# SCH_MODULO_LORA.net
KiCad netlist of a schematic drawn in Altium Designer
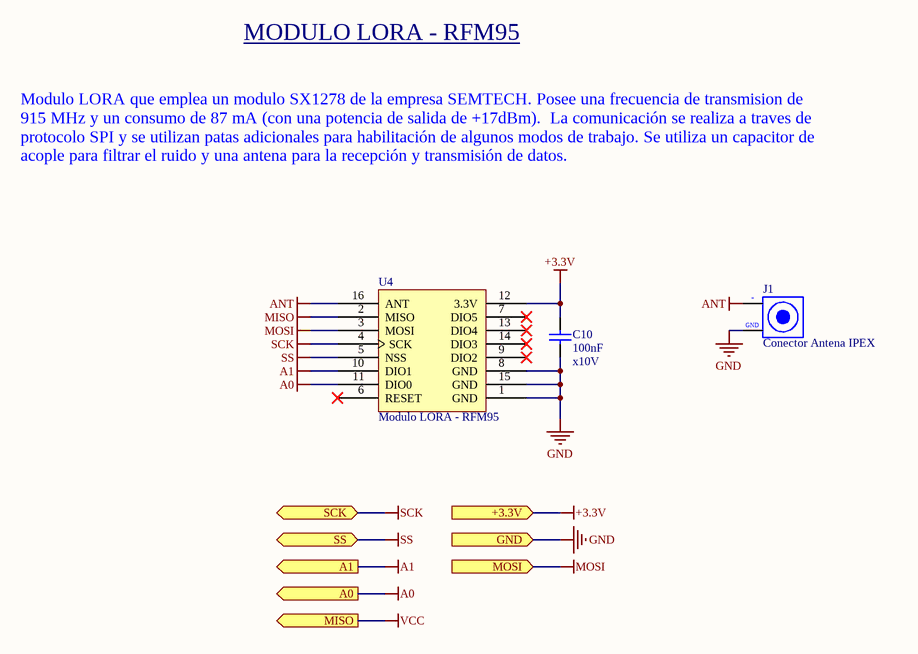
[diagram p0: SCH_MODULO_LORA.SchDoc]

(export (version "E")
  (design (tool "Eeschema 10.0.6"))
  (components
    (comp (ref "C10")
      (value "100nF")
      (footprint "RAD-0.3")
      (description "Capacitor")
      (fields
        (field (name "VOLTAGE") "x10V")
        (field (name "Comment") "Capacitor - Común")
        (field (name "PUBLISHER") "Altium Limited")
      )
      (libsource (lib "LIB_COLLAR") (part "Capacitor - Común"))
    )
    (comp (ref "J1")
      (value "Conector Antena IPEX")
      (description "IPEX MHF3")
      (libsource (lib "LIB_COLLAR") (part "Conector Antena IPEX"))
    )
    (comp (ref "U4")
      (value "Modulo LORA - RFM95")
      (description "RFM95-915-S2")
      (libsource (lib "LIB_COLLAR") (part "Modulo LORA - RFM95"))
    )
  )
  (nets
    (net (code "1") (name "+3.3V") (class "Default")
      (node (ref "C10") (pin "2") (pinfunction "2_2") (pintype "passive"))
      (node (ref "U4") (pin "12") (pinfunction "3.3V_12") (pintype "passive"))
    )
    (net (code "2") (name "A0") (class "Default")
      (node (ref "U4") (pin "11") (pinfunction "DIO0_11") (pintype "passive"))
    )
    (net (code "3") (name "A1") (class "Default")
      (node (ref "U4") (pin "10") (pinfunction "DIO1_10") (pintype "passive"))
    )
    (net (code "4") (name "ANT") (class "Default")
      (node (ref "J1") (pin "1") (pinfunction "ANT_1") (pintype "passive"))
      (node (ref "U4") (pin "16") (pinfunction "ANT_16") (pintype "passive"))
    )
    (net (code "5") (name "GND") (class "Default")
      (node (ref "C10") (pin "1") (pinfunction "1_1") (pintype "passive"))
      (node (ref "J1") (pin "2") (pinfunction "2_2") (pintype "passive"))
      (node (ref "U4") (pin "1") (pinfunction "GND_1") (pintype "passive"))
      (node (ref "U4") (pin "15") (pinfunction "GND_15") (pintype "passive"))
      (node (ref "U4") (pin "8") (pinfunction "GND_8") (pintype "passive"))
    )
    (net (code "6") (name "MISO") (class "Default")
      (node (ref "U4") (pin "2") (pinfunction "MISO_2") (pintype "passive"))
    )
    (net (code "7") (name "MOSI") (class "Default")
      (node (ref "U4") (pin "3") (pinfunction "MOSI_3") (pintype "passive"))
    )
    (net (code "8") (name "SCK") (class "Default")
      (node (ref "U4") (pin "4") (pinfunction "SCK_4") (pintype "passive"))
    )
    (net (code "9") (name "SS") (class "Default")
      (node (ref "U4") (pin "5") (pinfunction "NSS_5") (pintype "passive"))
    )
    (net (code "10") (name "unconnected-(U4-DIO2-Pad9)") (class "Default")
      (node (ref "U4") (pin "9") (pinfunction "DIO2_9") (pintype "passive+no_connect"))
    )
    (net (code "11") (name "unconnected-(U4-DIO3-Pad14)") (class "Default")
      (node (ref "U4") (pin "14") (pinfunction "DIO3_14") (pintype "passive+no_connect"))
    )
    (net (code "12") (name "unconnected-(U4-DIO4-Pad13)") (class "Default")
      (node (ref "U4") (pin "13") (pinfunction "DIO4_13") (pintype "passive+no_connect"))
    )
    (net (code "13") (name "unconnected-(U4-DIO5-Pad7)") (class "Default")
      (node (ref "U4") (pin "7") (pinfunction "DIO5_7") (pintype "passive+no_connect"))
    )
    (net (code "14") (name "unconnected-(U4-RESET-Pad6)") (class "Default")
      (node (ref "U4") (pin "6") (pinfunction "RESET_6") (pintype "passive+no_connect"))
    )
  )
)
